# Marklin_BR_128_LED.net
KiCad netlist of a schematic drawn in EAGLE
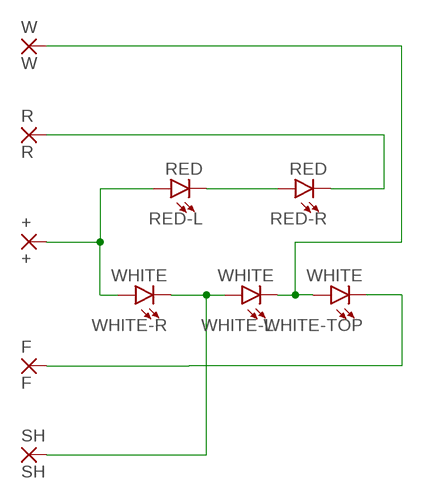
[diagram p0: schematic, sheet 1]

(export (version "E")
  (design (tool "Eeschema 10.0.6"))
  (components
    (comp (ref "+")
      (value "+")
      (footprint "eagle-import:SMD1,27-2,54")
      (libsource (lib "eagle-import") (part "SMD2"))
    )
    (comp (ref "F")
      (value "F")
      (footprint "eagle-import:SMD1,27-2,54")
      (libsource (lib "eagle-import") (part "SMD2"))
    )
    (comp (ref "R")
      (value "R")
      (footprint "eagle-import:SMD1,27-2,54")
      (libsource (lib "eagle-import") (part "SMD2"))
    )
    (comp (ref "RED-L")
      (value "RED")
      (footprint "eagle-import:LED-0603")
      (libsource (lib "eagle-import") (part "LED-RED0603"))
    )
    (comp (ref "RED-R")
      (value "RED")
      (footprint "eagle-import:LED-0603")
      (libsource (lib "eagle-import") (part "LED-RED0603"))
    )
    (comp (ref "SH")
      (value "SH")
      (footprint "eagle-import:SMD1,27-2,54")
      (libsource (lib "eagle-import") (part "SMD2"))
    )
    (comp (ref "W")
      (value "W")
      (footprint "eagle-import:SMD1,27-2,54")
      (libsource (lib "eagle-import") (part "SMD2"))
    )
    (comp (ref "WHITE-L")
      (value "WHITE")
      (footprint "eagle-import:LED-0603")
      (libsource (lib "eagle-import") (part "LED-WHITE0603"))
    )
    (comp (ref "WHITE-R")
      (value "WHITE")
      (footprint "eagle-import:LED-0603")
      (libsource (lib "eagle-import") (part "LED-WHITE0603"))
    )
    (comp (ref "WHITE-TOP")
      (value "WHITE")
      (footprint "eagle-import:LED-0603")
      (libsource (lib "eagle-import") (part "LED-WHITE0603"))
    )
  )
  (nets
    (net (code "1") (name "Net-(+-P)") (class "Default")
      (node (ref "+") (pin "1") (pinfunction "P_1") (pintype "passive"))
      (node (ref "RED-L") (pin "A") (pinfunction "A_A") (pintype "passive"))
      (node (ref "WHITE-R") (pin "A") (pinfunction "A_A") (pintype "passive"))
    )
    (net (code "2") (name "Net-(F-P)") (class "Default")
      (node (ref "F") (pin "1") (pinfunction "P_1") (pintype "passive"))
      (node (ref "WHITE-TOP") (pin "C") (pinfunction "C_C") (pintype "passive"))
    )
    (net (code "3") (name "Net-(R-P)") (class "Default")
      (node (ref "R") (pin "1") (pinfunction "P_1") (pintype "passive"))
      (node (ref "RED-R") (pin "C") (pinfunction "C_C") (pintype "passive"))
    )
    (net (code "4") (name "Net-(RED-L-PadC)") (class "Default")
      (node (ref "RED-L") (pin "C") (pinfunction "C_C") (pintype "passive"))
      (node (ref "RED-R") (pin "A") (pinfunction "A_A") (pintype "passive"))
    )
    (net (code "5") (name "Net-(SH-P)") (class "Default")
      (node (ref "SH") (pin "1") (pinfunction "P_1") (pintype "passive"))
      (node (ref "WHITE-L") (pin "A") (pinfunction "A_A") (pintype "passive"))
      (node (ref "WHITE-R") (pin "C") (pinfunction "C_C") (pintype "passive"))
    )
    (net (code "6") (name "Net-(W-P)") (class "Default")
      (node (ref "W") (pin "1") (pinfunction "P_1") (pintype "passive"))
      (node (ref "WHITE-L") (pin "C") (pinfunction "C_C") (pintype "passive"))
      (node (ref "WHITE-TOP") (pin "A") (pinfunction "A_A") (pintype "passive"))
    )
  )
)
